# ac_and_dc_measurement.net
KiCad netlist of a schematic drawn in EAGLE
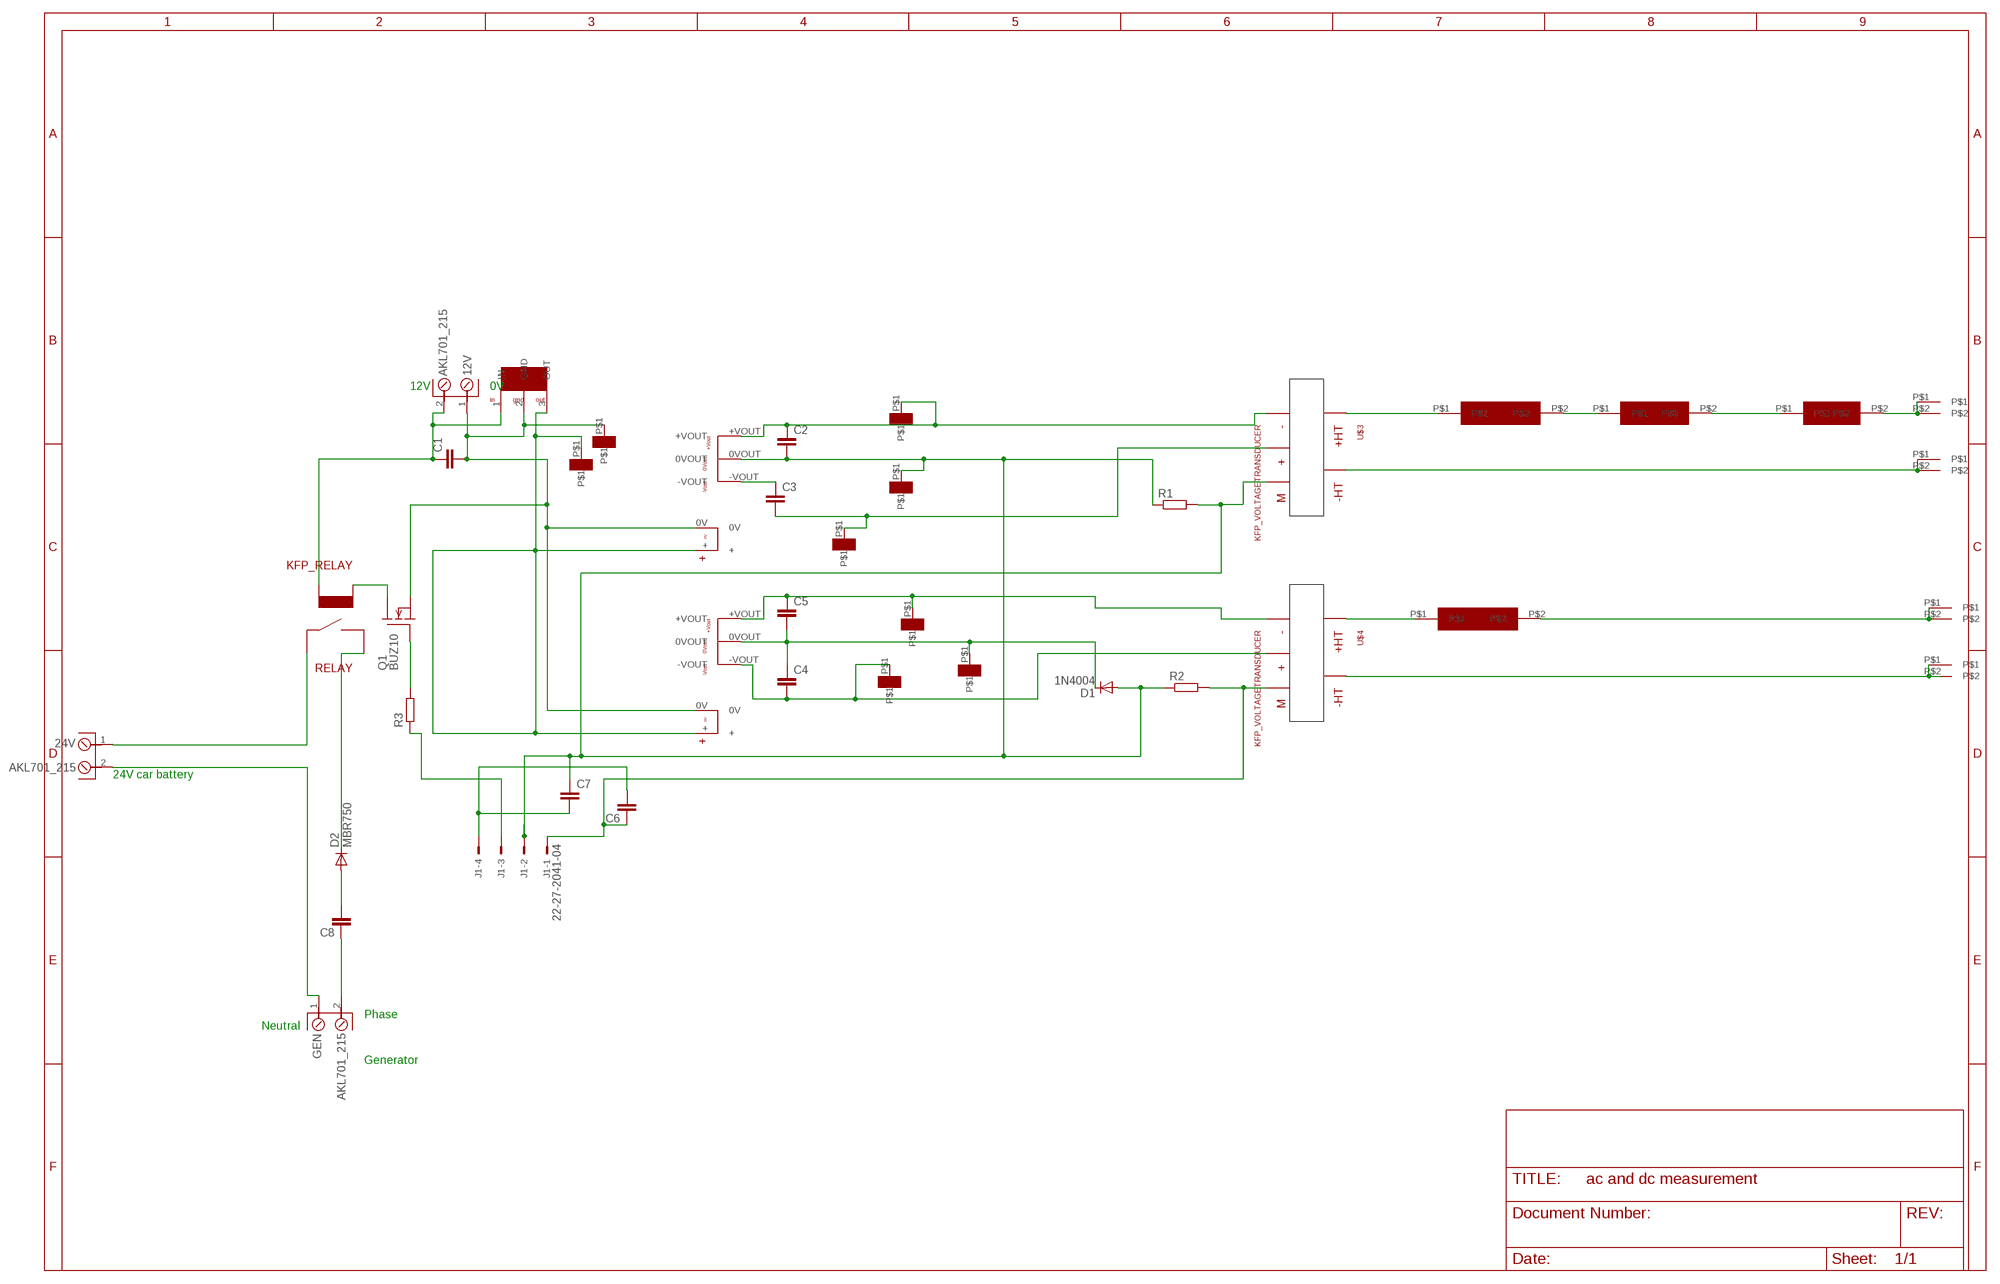
[diagram p0: schematic, sheet 1]

(export (version "E")
  (design (tool "Eeschema 10.0.6"))
  (components
    (comp (ref "5V")
      (value "KFP_VOL_REG")
      (footprint "eagle-import:TO220")
      (libsource (lib "eagle-import") (part "KFP_VOL_REG"))
    )
    (comp (ref "12V")
      (value "AKL701_215")
      (footprint "eagle-import:AKL701_2_15")
      (libsource (lib "eagle-import") (part "AKL701_215"))
    )
    (comp (ref "24V")
      (value "AKL701_215")
      (footprint "eagle-import:AKL701_2_15")
      (libsource (lib "eagle-import") (part "AKL701_215"))
    )
    (comp (ref "C1")
      (value "C-EU025-024X044")
      (footprint "eagle-import:C025-024X044")
      (libsource (lib "eagle-import") (part "C-EU025-024X044"))
    )
    (comp (ref "C2")
      (value "C-EU025-024X044")
      (footprint "eagle-import:C025-024X044")
      (libsource (lib "eagle-import") (part "C-EU025-024X044"))
    )
    (comp (ref "C3")
      (value "C-EU025-024X044")
      (footprint "eagle-import:C025-024X044")
      (libsource (lib "eagle-import") (part "C-EU025-024X044"))
    )
    (comp (ref "C4")
      (value "C-EU025-024X044")
      (footprint "eagle-import:C025-024X044")
      (libsource (lib "eagle-import") (part "C-EU025-024X044"))
    )
    (comp (ref "C5")
      (value "C-EU025-024X044")
      (footprint "eagle-import:C025-024X044")
      (libsource (lib "eagle-import") (part "C-EU025-024X044"))
    )
    (comp (ref "C6")
      (value "C-EU025-024X044")
      (footprint "eagle-import:C025-024X044")
      (libsource (lib "eagle-import") (part "C-EU025-024X044"))
    )
    (comp (ref "C7")
      (value "C-EU025-024X044")
      (footprint "eagle-import:C025-024X044")
      (libsource (lib "eagle-import") (part "C-EU025-024X044"))
    )
    (comp (ref "C8")
      (value "C-EU025-030X050")
      (footprint "eagle-import:C025-030X050")
      (libsource (lib "eagle-import") (part "C-EU025-030X050"))
    )
    (comp (ref "D1")
      (value "1N4004")
      (footprint "eagle-import:DO41-10")
      (libsource (lib "eagle-import") (part "1N4004"))
    )
    (comp (ref "D2")
      (value "MBR750")
      (footprint "eagle-import:TO220AC")
      (libsource (lib "eagle-import") (part "MBR750"))
    )
    (comp (ref "GEN")
      (value "AKL701_215")
      (footprint "eagle-import:AKL701_2_15")
      (libsource (lib "eagle-import") (part "AKL701_215"))
    )
    (comp (ref "J1")
      (value "22-27-2041-04")
      (footprint "eagle-import:6410-04")
      (libsource (lib "eagle-import") (part "22-?-0427-2041"))
    )
    (comp (ref "Q1")
      (value "BUZ10")
      (footprint "eagle-import:TO220")
      (libsource (lib "eagle-import") (part "BUZ10"))
    )
    (comp (ref "R1")
      (value "R-EU_0204/7")
      (footprint "eagle-import:0204_7")
      (libsource (lib "eagle-import") (part "R-EU_0204/7"))
    )
    (comp (ref "R2")
      (value "R-EU_0204/7")
      (footprint "eagle-import:0204_7")
      (libsource (lib "eagle-import") (part "R-EU_0204/7"))
    )
    (comp (ref "R3")
      (value "R-EU_0204/7")
      (footprint "eagle-import:0204_7")
      (libsource (lib "eagle-import") (part "R-EU_0204/7"))
    )
    (comp (ref "RELAY")
      (value "KFP_RELAY")
      (footprint "eagle-import:KFP_RELAYSPST")
      (libsource (lib "eagle-import") (part "KFP_RELAY"))
    )
    (comp (ref "U$1")
      (value "KFP_DC_DC")
      (footprint "eagle-import:KFP_DC-DC")
      (libsource (lib "eagle-import") (part "KFP_DC_DC"))
    )
    (comp (ref "U$2")
      (value "KFP_DC_DC")
      (footprint "eagle-import:KFP_DC-DC")
      (libsource (lib "eagle-import") (part "KFP_DC_DC"))
    )
    (comp (ref "U$3")
      (value "KFP_VOLTAGETRANSDUCER")
      (footprint "eagle-import:KFP_VOLTAGETRANSDUCER")
      (libsource (lib "eagle-import") (part "KFP_VOLTAGETRANSDUCER"))
    )
    (comp (ref "U$4")
      (value "KFP_VOLTAGETRANSDUCER")
      (footprint "eagle-import:KFP_VOLTAGETRANSDUCER")
      (libsource (lib "eagle-import") (part "KFP_VOLTAGETRANSDUCER"))
    )
    (comp (ref "U$5")
      (value "KFP_33K")
      (footprint "eagle-import:KFP_33K")
      (libsource (lib "eagle-import") (part "KFP_33K"))
    )
    (comp (ref "U$6")
      (value "KFP_33K")
      (footprint "eagle-import:KFP_33K")
      (libsource (lib "eagle-import") (part "KFP_33K"))
    )
    (comp (ref "U$7")
      (value "KFP_22K")
      (footprint "eagle-import:KFP_22K")
      (libsource (lib "eagle-import") (part "KFP_22K"))
    )
    (comp (ref "U$8")
      (value "KFP_4.7K")
      (footprint "eagle-import:KFP_18K")
      (libsource (lib "eagle-import") (part "KFP_4.7K"))
    )
    (comp (ref "U$9")
      (value "HIGH_AMP_TERMINAL")
      (footprint "eagle-import:HIGH_AMP_TERMINAL")
      (libsource (lib "eagle-import") (part "HIGH_AMP_TERMINAL"))
    )
    (comp (ref "U$11")
      (value "HIGH_AMP_TERMINAL")
      (footprint "eagle-import:HIGH_AMP_TERMINAL")
      (libsource (lib "eagle-import") (part "HIGH_AMP_TERMINAL"))
    )
    (comp (ref "U$12")
      (value "HIGH_AMP_TERMINAL")
      (footprint "eagle-import:HIGH_AMP_TERMINAL")
      (libsource (lib "eagle-import") (part "HIGH_AMP_TERMINAL"))
    )
    (comp (ref "U$13")
      (value "HIGH_AMP_TERMINAL")
      (footprint "eagle-import:HIGH_AMP_TERMINAL")
      (libsource (lib "eagle-import") (part "HIGH_AMP_TERMINAL"))
    )
    (comp (ref "U$14")
      (value "KFP_TEST")
      (footprint "eagle-import:KFP_TEST")
      (libsource (lib "eagle-import") (part "KFP_TEST"))
    )
    (comp (ref "U$15")
      (value "KFP_TEST")
      (footprint "eagle-import:KFP_TEST")
      (libsource (lib "eagle-import") (part "KFP_TEST"))
    )
    (comp (ref "U$16")
      (value "KFP_TEST")
      (footprint "eagle-import:KFP_TEST")
      (libsource (lib "eagle-import") (part "KFP_TEST"))
    )
    (comp (ref "U$17")
      (value "KFP_TEST")
      (footprint "eagle-import:KFP_TEST")
      (libsource (lib "eagle-import") (part "KFP_TEST"))
    )
    (comp (ref "U$18")
      (value "KFP_TEST")
      (footprint "eagle-import:KFP_TEST")
      (libsource (lib "eagle-import") (part "KFP_TEST"))
    )
    (comp (ref "U$19")
      (value "KFP_TEST")
      (footprint "eagle-import:KFP_TEST")
      (libsource (lib "eagle-import") (part "KFP_TEST"))
    )
    (comp (ref "U$20")
      (value "KFP_TEST")
      (footprint "eagle-import:KFP_TEST")
      (libsource (lib "eagle-import") (part "KFP_TEST"))
    )
    (comp (ref "U$21")
      (value "KFP_TEST")
      (footprint "eagle-import:KFP_TEST")
      (libsource (lib "eagle-import") (part "KFP_TEST"))
    )
  )
  (nets
    (net (code "1") (name "Net-(5V-GND)") (class "Default")
      (node (ref "12V") (pin "1") (pinfunction "1_1") (pintype "passive"))
      (node (ref "5V") (pin "2") (pinfunction "GND_2") (pintype "bidirectional"))
      (node (ref "C1") (pin "2") (pinfunction "2_2") (pintype "passive"))
      (node (ref "Q1") (pin "3") (pinfunction "S_3") (pintype "passive"))
      (node (ref "U$1") (pin "0V") (pinfunction "0V_0V") (pintype "bidirectional"))
      (node (ref "U$2") (pin "0V") (pinfunction "0V_0V") (pintype "bidirectional"))
      (node (ref "U$21") (pin "P$1") (pinfunction "P$1_P$1") (pintype "bidirectional"))
    )
    (net (code "2") (name "Net-(5V-IN)") (class "Default")
      (node (ref "12V") (pin "2") (pinfunction "2_2") (pintype "passive"))
      (node (ref "5V") (pin "1") (pinfunction "IN_1") (pintype "bidirectional"))
      (node (ref "C1") (pin "1") (pinfunction "1_1") (pintype "passive"))
      (node (ref "RELAY") (pin "A2") (pinfunction "A2_A2") (pintype "bidirectional"))
    )
    (net (code "3") (name "Net-(5V-OUT)") (class "Default")
      (node (ref "5V") (pin "3") (pinfunction "OUT_3") (pintype "bidirectional"))
      (node (ref "U$1") (pin "+") (pinfunction "+_+") (pintype "bidirectional"))
      (node (ref "U$16") (pin "P$1") (pinfunction "P$1_P$1") (pintype "bidirectional"))
      (node (ref "U$2") (pin "+") (pinfunction "+_+") (pintype "bidirectional"))
    )
    (net (code "4") (name "Net-(24V-Pad1)") (class "Default")
      (node (ref "24V") (pin "1") (pinfunction "1_1") (pintype "passive"))
      (node (ref "RELAY") (pin "14") (pinfunction "14_14") (pintype "bidirectional"))
    )
    (net (code "5") (name "Net-(24V-Pad2)") (class "Default")
      (node (ref "24V") (pin "2") (pinfunction "2_2") (pintype "passive"))
      (node (ref "GEN") (pin "1") (pinfunction "1_1") (pintype "passive"))
    )
    (net (code "6") (name "Net-(C2-Pad1)") (class "Default")
      (node (ref "C2") (pin "1") (pinfunction "1_1") (pintype "passive"))
      (node (ref "U$1") (pin "+VOUT") (pinfunction "+VOUT_+VOUT") (pintype "bidirectional"))
      (node (ref "U$15") (pin "P$1") (pinfunction "P$1_P$1") (pintype "bidirectional"))
      (node (ref "U$3") (pin "-") (pinfunction "-_-") (pintype "bidirectional"))
    )
    (net (code "7") (name "Net-(C3-Pad1)") (class "Default")
      (node (ref "C3") (pin "1") (pinfunction "1_1") (pintype "passive"))
      (node (ref "U$1") (pin "-VOUT") (pinfunction "-VOUT_-VOUT") (pintype "bidirectional"))
    )
    (net (code "8") (name "Net-(C3-Pad2)") (class "Default")
      (node (ref "C3") (pin "2") (pinfunction "2_2") (pintype "passive"))
      (node (ref "U$14") (pin "P$1") (pinfunction "P$1_P$1") (pintype "bidirectional"))
      (node (ref "U$3") (pin "+") (pinfunction "+_+") (pintype "bidirectional"))
    )
    (net (code "9") (name "Net-(C4-Pad1)") (class "Default")
      (node (ref "C4") (pin "1") (pinfunction "1_1") (pintype "passive"))
      (node (ref "C5") (pin "2") (pinfunction "2_2") (pintype "passive"))
      (node (ref "D1") (pin "C") (pinfunction "C_C") (pintype "passive"))
      (node (ref "U$2") (pin "0VOUT") (pinfunction "0VOUT_0VOUT") (pintype "bidirectional"))
      (node (ref "U$20") (pin "P$1") (pinfunction "P$1_P$1") (pintype "bidirectional"))
    )
    (net (code "10") (name "Net-(C4-Pad2)") (class "Default")
      (node (ref "C4") (pin "2") (pinfunction "2_2") (pintype "passive"))
      (node (ref "U$18") (pin "P$1") (pinfunction "P$1_P$1") (pintype "bidirectional"))
      (node (ref "U$2") (pin "-VOUT") (pinfunction "-VOUT_-VOUT") (pintype "bidirectional"))
      (node (ref "U$4") (pin "+") (pinfunction "+_+") (pintype "bidirectional"))
    )
    (net (code "11") (name "Net-(C5-Pad1)") (class "Default")
      (node (ref "C5") (pin "1") (pinfunction "1_1") (pintype "passive"))
      (node (ref "U$17") (pin "P$1") (pinfunction "P$1_P$1") (pintype "bidirectional"))
      (node (ref "U$2") (pin "+VOUT") (pinfunction "+VOUT_+VOUT") (pintype "bidirectional"))
      (node (ref "U$4") (pin "-") (pinfunction "-_-") (pintype "bidirectional"))
    )
    (net (code "12") (name "Net-(C8-Pad1)") (class "Default")
      (node (ref "C8") (pin "1") (pinfunction "1_1") (pintype "passive"))
      (node (ref "GEN") (pin "2") (pinfunction "2_2") (pintype "passive"))
    )
    (net (code "13") (name "Net-(C8-Pad2)") (class "Default")
      (node (ref "C8") (pin "2") (pinfunction "2_2") (pintype "passive"))
      (node (ref "D2") (pin "A") (pinfunction "A_A") (pintype "passive"))
    )
    (net (code "14") (name "Net-(D2-PadC)") (class "Default")
      (node (ref "D2") (pin "C") (pinfunction "C_C") (pintype "passive"))
      (node (ref "RELAY") (pin "11") (pinfunction "11_11") (pintype "bidirectional"))
    )
    (net (code "15") (name "Net-(J1A-S)") (class "Default")
      (node (ref "C6") (pin "1") (pinfunction "1_1") (pintype "passive"))
      (node (ref "J1") (pin "1") (pinfunction "S_1") (pintype "passive"))
      (node (ref "R2") (pin "2") (pinfunction "2_2") (pintype "passive"))
      (node (ref "U$4") (pin "M") (pinfunction "M_M") (pintype "bidirectional"))
    )
    (net (code "16") (name "Net-(J1B-S)") (class "Default")
      (node (ref "C2") (pin "2") (pinfunction "2_2") (pintype "passive"))
      (node (ref "C7") (pin "1") (pinfunction "1_1") (pintype "passive"))
      (node (ref "D1") (pin "A") (pinfunction "A_A") (pintype "passive"))
      (node (ref "J1") (pin "2") (pinfunction "S_2") (pintype "passive"))
      (node (ref "R1") (pin "1") (pinfunction "1_1") (pintype "passive"))
      (node (ref "R1") (pin "2") (pinfunction "2_2") (pintype "passive"))
      (node (ref "R2") (pin "1") (pinfunction "1_1") (pintype "passive"))
      (node (ref "U$1") (pin "0VOUT") (pinfunction "0VOUT_0VOUT") (pintype "bidirectional"))
      (node (ref "U$19") (pin "P$1") (pinfunction "P$1_P$1") (pintype "bidirectional"))
      (node (ref "U$3") (pin "M") (pinfunction "M_M") (pintype "bidirectional"))
    )
    (net (code "17") (name "Net-(J1C-S)") (class "Default")
      (node (ref "J1") (pin "3") (pinfunction "S_3") (pintype "passive"))
      (node (ref "R3") (pin "1") (pinfunction "1_1") (pintype "passive"))
    )
    (net (code "18") (name "Net-(J1D-S)") (class "Default")
      (node (ref "C6") (pin "2") (pinfunction "2_2") (pintype "passive"))
      (node (ref "C7") (pin "2") (pinfunction "2_2") (pintype "passive"))
      (node (ref "J1") (pin "4") (pinfunction "S_4") (pintype "passive"))
    )
    (net (code "19") (name "Net-(Q1-D)") (class "Default")
      (node (ref "Q1") (pin "2") (pinfunction "D_2") (pintype "passive"))
      (node (ref "RELAY") (pin "A1") (pinfunction "A1_A1") (pintype "bidirectional"))
    )
    (net (code "20") (name "Net-(Q1-G)") (class "Default")
      (node (ref "Q1") (pin "1") (pinfunction "G_1") (pintype "passive"))
      (node (ref "R3") (pin "2") (pinfunction "2_2") (pintype "passive"))
    )
    (net (code "21") (name "Net-(U$3-+HT)") (class "Default")
      (node (ref "U$3") (pin "+HT]") (pinfunction "+HT_+HT]") (pintype "bidirectional"))
      (node (ref "U$6") (pin "P$1") (pinfunction "P$1_P$1") (pintype "bidirectional"))
    )
    (net (code "22") (name "Net-(U$4-+HT)") (class "Default")
      (node (ref "U$4") (pin "+HT]") (pinfunction "+HT_+HT]") (pintype "bidirectional"))
      (node (ref "U$5") (pin "P$1") (pinfunction "P$1_P$1") (pintype "bidirectional"))
    )
    (net (code "23") (name "Net-(U$6-PadP$2)") (class "Default")
      (node (ref "U$6") (pin "P$2") (pinfunction "P$2_P$2") (pintype "bidirectional"))
      (node (ref "U$7") (pin "P$1") (pinfunction "P$1_P$1") (pintype "bidirectional"))
    )
    (net (code "24") (name "Net-(U$7-P$3)") (class "Default")
      (node (ref "U$7") (pin "P$2") (pinfunction "P$3_P$2") (pintype "bidirectional"))
      (node (ref "U$8") (pin "P$1") (pinfunction "P$1_P$1") (pintype "bidirectional"))
    )
    (net (code "25") (name "Net-(U$8-PadP$2)") (class "Default")
      (node (ref "U$8") (pin "P$2") (pinfunction "P$2_P$2") (pintype "bidirectional"))
      (node (ref "U$9") (pin "P$1") (pinfunction "P$1_P$1") (pintype "bidirectional"))
      (node (ref "U$9") (pin "P$2") (pinfunction "P$2_P$2") (pintype "bidirectional"))
    )
    (net (code "26") (name "Net-(U$11-PadP$1)") (class "Default")
      (node (ref "U$11") (pin "P$1") (pinfunction "P$1_P$1") (pintype "bidirectional"))
      (node (ref "U$11") (pin "P$2") (pinfunction "P$2_P$2") (pintype "bidirectional"))
      (node (ref "U$3") (pin "-HT") (pinfunction "-HT_-HT") (pintype "bidirectional"))
    )
    (net (code "27") (name "Net-(U$12-PadP$1)") (class "Default")
      (node (ref "U$12") (pin "P$1") (pinfunction "P$1_P$1") (pintype "bidirectional"))
      (node (ref "U$12") (pin "P$2") (pinfunction "P$2_P$2") (pintype "bidirectional"))
      (node (ref "U$5") (pin "P$2") (pinfunction "P$2_P$2") (pintype "bidirectional"))
    )
    (net (code "28") (name "Net-(U$13-PadP$1)") (class "Default")
      (node (ref "U$13") (pin "P$1") (pinfunction "P$1_P$1") (pintype "bidirectional"))
      (node (ref "U$13") (pin "P$2") (pinfunction "P$2_P$2") (pintype "bidirectional"))
      (node (ref "U$4") (pin "-HT") (pinfunction "-HT_-HT") (pintype "bidirectional"))
    )
  )
)
